# Power.net
KiCad netlist of a schematic drawn in EAGLE
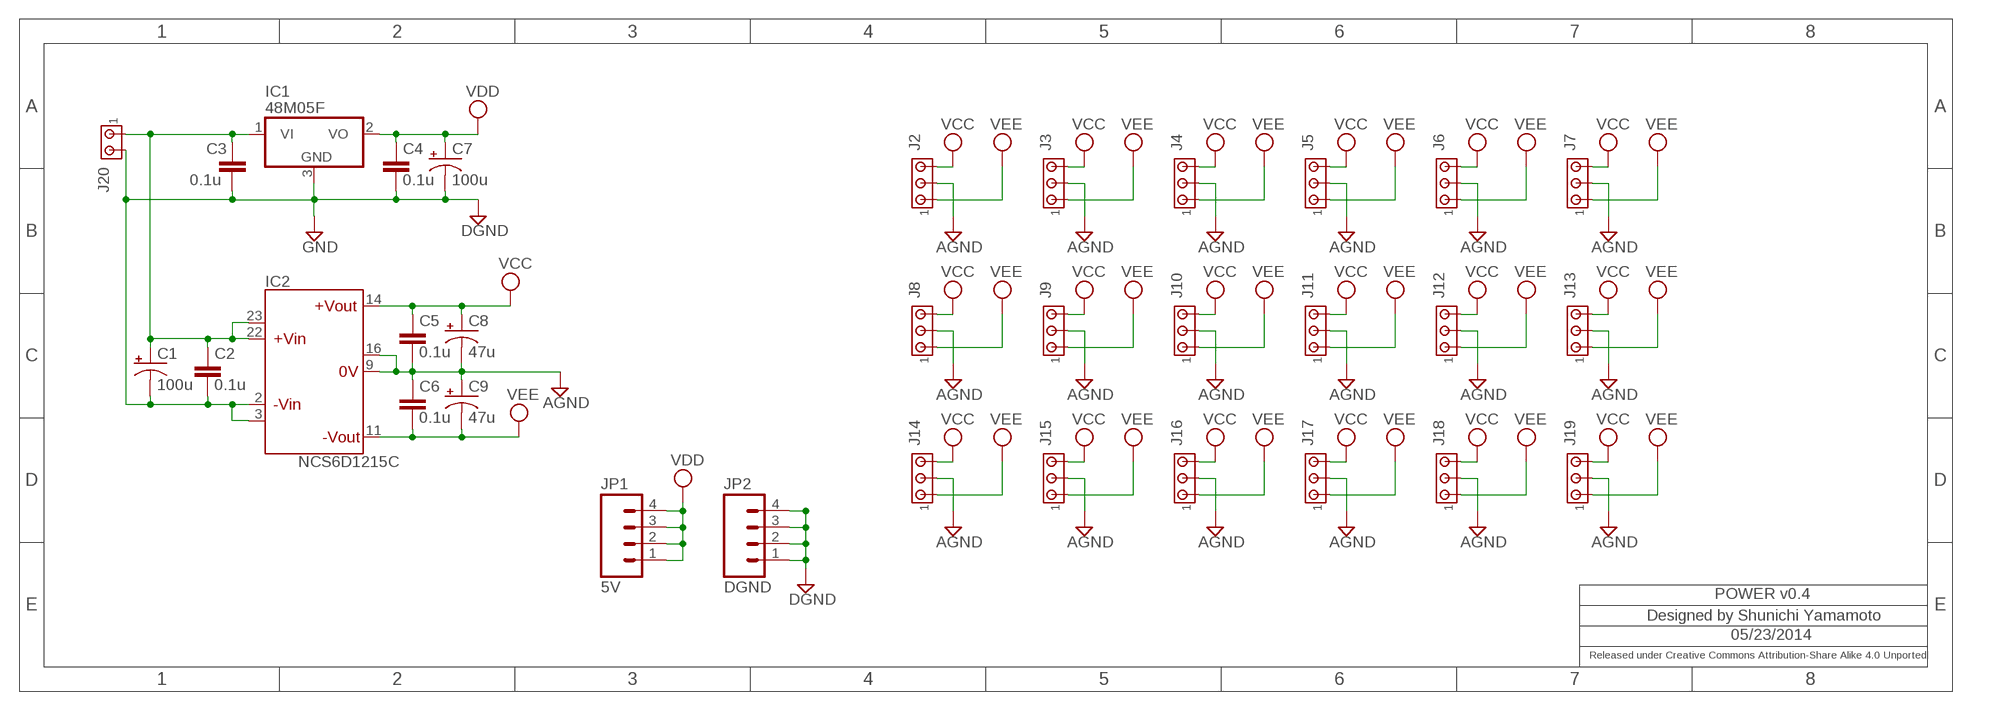
[diagram p0: schematic, sheet 1]

(export (version "E")
  (design (tool "Eeschema 10.0.6"))
  (components
    (comp (ref "C1")
      (value "100u")
      (footprint "eagle-import:UD-6,3X7,7_NICHICON")
      (libsource (lib "eagle-import") (part "CPOL-USUD-6,3X7,7"))
    )
    (comp (ref "C2")
      (value "0.1u")
      (footprint "eagle-import:C2012")
      (libsource (lib "eagle-import") (part "C-EUC2012"))
    )
    (comp (ref "C3")
      (value "0.1u")
      (footprint "eagle-import:C2012")
      (libsource (lib "eagle-import") (part "C-EUC2012"))
    )
    (comp (ref "C4")
      (value "0.1u")
      (footprint "eagle-import:C2012")
      (libsource (lib "eagle-import") (part "C-EUC2012"))
    )
    (comp (ref "C5")
      (value "0.1u")
      (footprint "eagle-import:C2012")
      (libsource (lib "eagle-import") (part "C-EUC2012"))
    )
    (comp (ref "C6")
      (value "0.1u")
      (footprint "eagle-import:C2012")
      (libsource (lib "eagle-import") (part "C-EUC2012"))
    )
    (comp (ref "C7")
      (value "100u")
      (footprint "eagle-import:UD-6,3X7,7_NICHICON")
      (libsource (lib "eagle-import") (part "CPOL-USUD-6,3X7,7"))
    )
    (comp (ref "C8")
      (value "47u")
      (footprint "eagle-import:UD-5X5,8_NICHICON")
      (libsource (lib "eagle-import") (part "CPOL-USUD-5X5,8"))
    )
    (comp (ref "C9")
      (value "47u")
      (footprint "eagle-import:UD-5X5,8_NICHICON")
      (libsource (lib "eagle-import") (part "CPOL-USUD-5X5,8"))
    )
    (comp (ref "IC1")
      (value "48M05F")
      (footprint "eagle-import:TO252")
      (libsource (lib "eagle-import") (part "78DT05"))
    )
    (comp (ref "IC2")
      (value "NCS6D1215C")
      (footprint "eagle-import:NCS6D1215C")
      (libsource (lib "eagle-import") (part "NCS6D1215C"))
    )
    (comp (ref "J2")
      (value "MTA03-156")
      (footprint "eagle-import:1X3MTA")
      (libsource (lib "eagle-import") (part "MTA03-156"))
    )
    (comp (ref "J3")
      (value "MTA03-156")
      (footprint "eagle-import:1X3MTA")
      (libsource (lib "eagle-import") (part "MTA03-156"))
    )
    (comp (ref "J4")
      (value "MTA03-156")
      (footprint "eagle-import:1X3MTA")
      (libsource (lib "eagle-import") (part "MTA03-156"))
    )
    (comp (ref "J5")
      (value "MTA03-156")
      (footprint "eagle-import:1X3MTA")
      (libsource (lib "eagle-import") (part "MTA03-156"))
    )
    (comp (ref "J6")
      (value "MTA03-156")
      (footprint "eagle-import:1X3MTA")
      (libsource (lib "eagle-import") (part "MTA03-156"))
    )
    (comp (ref "J7")
      (value "MTA03-156")
      (footprint "eagle-import:1X3MTA")
      (libsource (lib "eagle-import") (part "MTA03-156"))
    )
    (comp (ref "J8")
      (value "MTA03-156")
      (footprint "eagle-import:1X3MTA")
      (libsource (lib "eagle-import") (part "MTA03-156"))
    )
    (comp (ref "J9")
      (value "MTA03-156")
      (footprint "eagle-import:1X3MTA")
      (libsource (lib "eagle-import") (part "MTA03-156"))
    )
    (comp (ref "J10")
      (value "MTA03-156")
      (footprint "eagle-import:1X3MTA")
      (libsource (lib "eagle-import") (part "MTA03-156"))
    )
    (comp (ref "J11")
      (value "MTA03-156")
      (footprint "eagle-import:1X3MTA")
      (libsource (lib "eagle-import") (part "MTA03-156"))
    )
    (comp (ref "J12")
      (value "MTA03-156")
      (footprint "eagle-import:1X3MTA")
      (libsource (lib "eagle-import") (part "MTA03-156"))
    )
    (comp (ref "J13")
      (value "MTA03-156")
      (footprint "eagle-import:1X3MTA")
      (libsource (lib "eagle-import") (part "MTA03-156"))
    )
    (comp (ref "J14")
      (value "MTA03-156")
      (footprint "eagle-import:1X3MTA")
      (libsource (lib "eagle-import") (part "MTA03-156"))
    )
    (comp (ref "J15")
      (value "MTA03-156")
      (footprint "eagle-import:1X3MTA")
      (libsource (lib "eagle-import") (part "MTA03-156"))
    )
    (comp (ref "J16")
      (value "MTA03-156")
      (footprint "eagle-import:1X3MTA")
      (libsource (lib "eagle-import") (part "MTA03-156"))
    )
    (comp (ref "J17")
      (value "MTA03-156")
      (footprint "eagle-import:1X3MTA")
      (libsource (lib "eagle-import") (part "MTA03-156"))
    )
    (comp (ref "J18")
      (value "MTA03-156")
      (footprint "eagle-import:1X3MTA")
      (libsource (lib "eagle-import") (part "MTA03-156"))
    )
    (comp (ref "J19")
      (value "MTA03-156")
      (footprint "eagle-import:1X3MTA")
      (libsource (lib "eagle-import") (part "MTA03-156"))
    )
    (comp (ref "J20")
      (value "MTA02-156")
      (footprint "eagle-import:1X2MTA")
      (libsource (lib "eagle-import") (part "MTA02-156"))
    )
    (comp (ref "JP1")
      (value "5V")
      (footprint "eagle-import:1X04")
      (libsource (lib "eagle-import") (part "M04PTH"))
    )
    (comp (ref "JP2")
      (value "DGND")
      (footprint "eagle-import:1X04")
      (libsource (lib "eagle-import") (part "M04PTH"))
    )
  )
  (nets
    (net (code "1") (name "AGND") (class "Default")
      (node (ref "C5") (pin "2") (pinfunction "2_2") (pintype "passive"))
      (node (ref "C6") (pin "1") (pinfunction "1_1") (pintype "passive"))
      (node (ref "C8") (pin "-") (pinfunction "-_-") (pintype "passive"))
      (node (ref "C9") (pin "+") (pinfunction "+_+") (pintype "passive"))
      (node (ref "IC2") (pin "16") (pinfunction "0V2_16") (pintype "bidirectional"))
      (node (ref "IC2") (pin "9") (pinfunction "0V_9") (pintype "bidirectional"))
      (node (ref "J10") (pin "2") (pinfunction "2_2") (pintype "passive"))
      (node (ref "J11") (pin "2") (pinfunction "2_2") (pintype "passive"))
      (node (ref "J12") (pin "2") (pinfunction "2_2") (pintype "passive"))
      (node (ref "J13") (pin "2") (pinfunction "2_2") (pintype "passive"))
      (node (ref "J14") (pin "2") (pinfunction "2_2") (pintype "passive"))
      (node (ref "J15") (pin "2") (pinfunction "2_2") (pintype "passive"))
      (node (ref "J16") (pin "2") (pinfunction "2_2") (pintype "passive"))
      (node (ref "J17") (pin "2") (pinfunction "2_2") (pintype "passive"))
      (node (ref "J18") (pin "2") (pinfunction "2_2") (pintype "passive"))
      (node (ref "J19") (pin "2") (pinfunction "2_2") (pintype "passive"))
      (node (ref "J2") (pin "2") (pinfunction "2_2") (pintype "passive"))
      (node (ref "J3") (pin "2") (pinfunction "2_2") (pintype "passive"))
      (node (ref "J4") (pin "2") (pinfunction "2_2") (pintype "passive"))
      (node (ref "J5") (pin "2") (pinfunction "2_2") (pintype "passive"))
      (node (ref "J6") (pin "2") (pinfunction "2_2") (pintype "passive"))
      (node (ref "J7") (pin "2") (pinfunction "2_2") (pintype "passive"))
      (node (ref "J8") (pin "2") (pinfunction "2_2") (pintype "passive"))
      (node (ref "J9") (pin "2") (pinfunction "2_2") (pintype "passive"))
    )
    (net (code "2") (name "DGND") (class "Default")
      (node (ref "C1") (pin "-") (pinfunction "-_-") (pintype "passive"))
      (node (ref "C2") (pin "2") (pinfunction "2_2") (pintype "passive"))
      (node (ref "C3") (pin "2") (pinfunction "2_2") (pintype "passive"))
      (node (ref "C4") (pin "2") (pinfunction "2_2") (pintype "passive"))
      (node (ref "C7") (pin "-") (pinfunction "-_-") (pintype "passive"))
      (node (ref "IC1") (pin "3") (pinfunction "GND_3") (pintype "passive"))
      (node (ref "IC2") (pin "2") (pinfunction "-VIN_2") (pintype "bidirectional"))
      (node (ref "IC2") (pin "3") (pinfunction "-VIN2_3") (pintype "bidirectional"))
      (node (ref "J20") (pin "2") (pinfunction "2_2") (pintype "passive"))
      (node (ref "JP2") (pin "1") (pinfunction "1_1") (pintype "passive"))
      (node (ref "JP2") (pin "2") (pinfunction "2_2") (pintype "passive"))
      (node (ref "JP2") (pin "3") (pinfunction "3_3") (pintype "passive"))
      (node (ref "JP2") (pin "4") (pinfunction "4_4") (pintype "passive"))
    )
    (net (code "3") (name "Net-(IC1-VI)") (class "Default")
      (node (ref "C1") (pin "+") (pinfunction "+_+") (pintype "passive"))
      (node (ref "C2") (pin "1") (pinfunction "1_1") (pintype "passive"))
      (node (ref "C3") (pin "1") (pinfunction "1_1") (pintype "passive"))
      (node (ref "IC1") (pin "1") (pinfunction "VI_1") (pintype "input"))
      (node (ref "IC2") (pin "22") (pinfunction "+VIN_22") (pintype "bidirectional"))
      (node (ref "IC2") (pin "23") (pinfunction "+VIN2_23") (pintype "bidirectional"))
      (node (ref "J20") (pin "1") (pinfunction "1_1") (pintype "passive"))
    )
    (net (code "4") (name "VCC") (class "Default")
      (node (ref "C5") (pin "1") (pinfunction "1_1") (pintype "passive"))
      (node (ref "C8") (pin "+") (pinfunction "+_+") (pintype "passive"))
      (node (ref "IC2") (pin "14") (pinfunction "+VOUT_14") (pintype "bidirectional"))
      (node (ref "J10") (pin "3") (pinfunction "3_3") (pintype "passive"))
      (node (ref "J11") (pin "3") (pinfunction "3_3") (pintype "passive"))
      (node (ref "J12") (pin "3") (pinfunction "3_3") (pintype "passive"))
      (node (ref "J13") (pin "3") (pinfunction "3_3") (pintype "passive"))
      (node (ref "J14") (pin "3") (pinfunction "3_3") (pintype "passive"))
      (node (ref "J15") (pin "3") (pinfunction "3_3") (pintype "passive"))
      (node (ref "J16") (pin "3") (pinfunction "3_3") (pintype "passive"))
      (node (ref "J17") (pin "3") (pinfunction "3_3") (pintype "passive"))
      (node (ref "J18") (pin "3") (pinfunction "3_3") (pintype "passive"))
      (node (ref "J19") (pin "3") (pinfunction "3_3") (pintype "passive"))
      (node (ref "J2") (pin "3") (pinfunction "3_3") (pintype "passive"))
      (node (ref "J3") (pin "3") (pinfunction "3_3") (pintype "passive"))
      (node (ref "J4") (pin "3") (pinfunction "3_3") (pintype "passive"))
      (node (ref "J5") (pin "3") (pinfunction "3_3") (pintype "passive"))
      (node (ref "J6") (pin "3") (pinfunction "3_3") (pintype "passive"))
      (node (ref "J7") (pin "3") (pinfunction "3_3") (pintype "passive"))
      (node (ref "J8") (pin "3") (pinfunction "3_3") (pintype "passive"))
      (node (ref "J9") (pin "3") (pinfunction "3_3") (pintype "passive"))
    )
    (net (code "5") (name "VDD") (class "Default")
      (node (ref "C4") (pin "1") (pinfunction "1_1") (pintype "passive"))
      (node (ref "C7") (pin "+") (pinfunction "+_+") (pintype "passive"))
      (node (ref "IC1") (pin "2") (pinfunction "VO_2") (pintype "passive"))
      (node (ref "JP1") (pin "1") (pinfunction "1_1") (pintype "passive"))
      (node (ref "JP1") (pin "2") (pinfunction "2_2") (pintype "passive"))
      (node (ref "JP1") (pin "3") (pinfunction "3_3") (pintype "passive"))
      (node (ref "JP1") (pin "4") (pinfunction "4_4") (pintype "passive"))
    )
    (net (code "6") (name "VEE") (class "Default")
      (node (ref "C6") (pin "2") (pinfunction "2_2") (pintype "passive"))
      (node (ref "C9") (pin "-") (pinfunction "-_-") (pintype "passive"))
      (node (ref "IC2") (pin "11") (pinfunction "-VOUT_11") (pintype "bidirectional"))
      (node (ref "J10") (pin "1") (pinfunction "1_1") (pintype "passive"))
      (node (ref "J11") (pin "1") (pinfunction "1_1") (pintype "passive"))
      (node (ref "J12") (pin "1") (pinfunction "1_1") (pintype "passive"))
      (node (ref "J13") (pin "1") (pinfunction "1_1") (pintype "passive"))
      (node (ref "J14") (pin "1") (pinfunction "1_1") (pintype "passive"))
      (node (ref "J15") (pin "1") (pinfunction "1_1") (pintype "passive"))
      (node (ref "J16") (pin "1") (pinfunction "1_1") (pintype "passive"))
      (node (ref "J17") (pin "1") (pinfunction "1_1") (pintype "passive"))
      (node (ref "J18") (pin "1") (pinfunction "1_1") (pintype "passive"))
      (node (ref "J19") (pin "1") (pinfunction "1_1") (pintype "passive"))
      (node (ref "J2") (pin "1") (pinfunction "1_1") (pintype "passive"))
      (node (ref "J3") (pin "1") (pinfunction "1_1") (pintype "passive"))
      (node (ref "J4") (pin "1") (pinfunction "1_1") (pintype "passive"))
      (node (ref "J5") (pin "1") (pinfunction "1_1") (pintype "passive"))
      (node (ref "J6") (pin "1") (pinfunction "1_1") (pintype "passive"))
      (node (ref "J7") (pin "1") (pinfunction "1_1") (pintype "passive"))
      (node (ref "J8") (pin "1") (pinfunction "1_1") (pintype "passive"))
      (node (ref "J9") (pin "1") (pinfunction "1_1") (pintype "passive"))
    )
  )
)
